# picoAvaR4.net
KiCad netlist of a schematic drawn in EAGLE
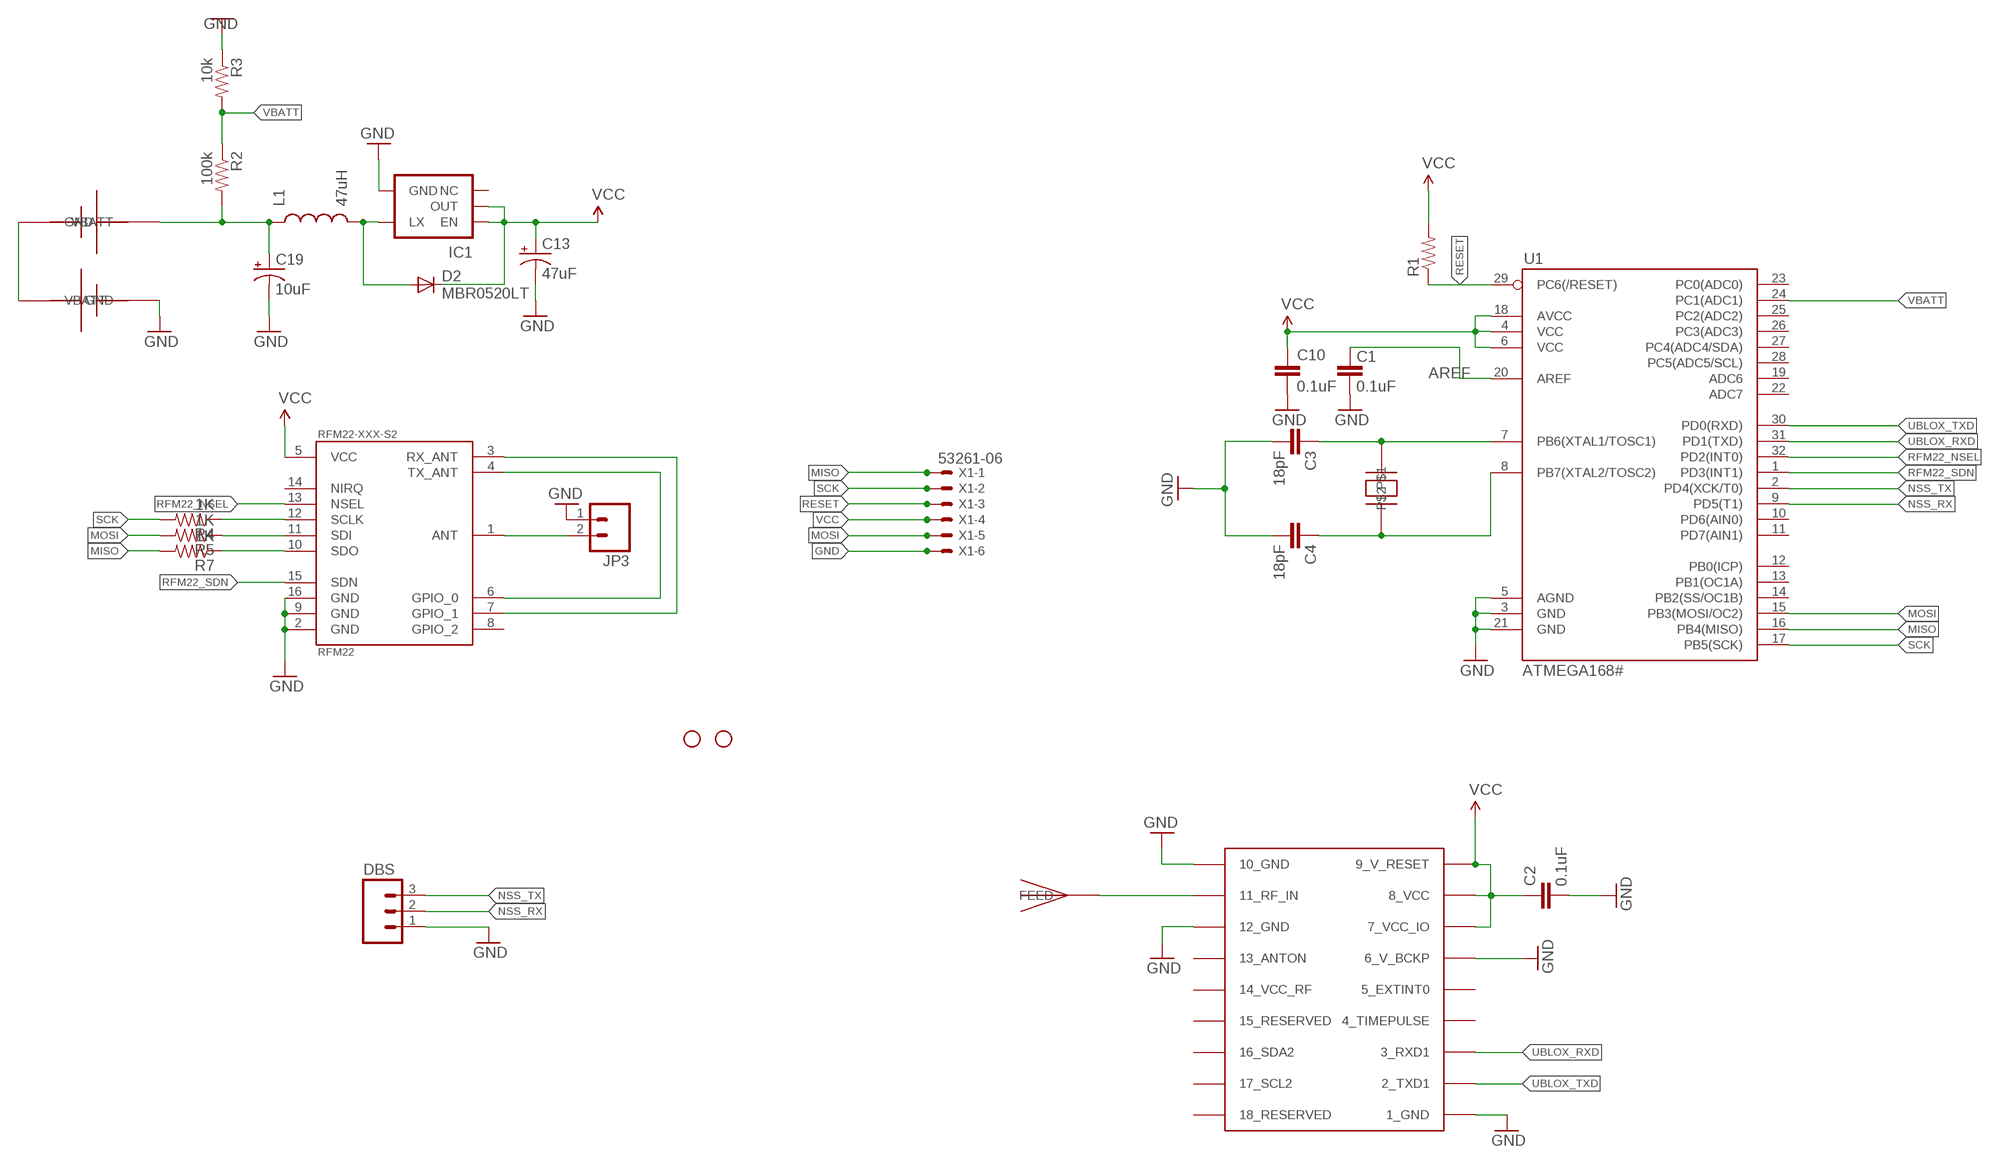
[diagram p0: schematic, sheet 1]

(export (version "E")
  (design (tool "Eeschema 10.0.6"))
  (components
    (comp (ref "C1")
      (value "0.1uF")
      (footprint "eagle-import:0402-CAP")
      (libsource (lib "eagle-import") (part "CAP0402-CAP"))
    )
    (comp (ref "C2")
      (value "0.1uF")
      (footprint "eagle-import:0402-CAP")
      (libsource (lib "eagle-import") (part "CAP0402-CAP"))
    )
    (comp (ref "C3")
      (value "18pF")
      (footprint "eagle-import:0402-CAP")
      (libsource (lib "eagle-import") (part "CAP0402-CAP"))
    )
    (comp (ref "C4")
      (value "18pF")
      (footprint "eagle-import:0402-CAP")
      (libsource (lib "eagle-import") (part "CAP0402-CAP"))
    )
    (comp (ref "C10")
      (value "0.1uF")
      (footprint "eagle-import:0402-CAP")
      (libsource (lib "eagle-import") (part "CAP0402-CAP"))
    )
    (comp (ref "C13")
      (value "47uF")
      (footprint "eagle-import:EIA3216")
      (libsource (lib "eagle-import") (part "CAP_POL1206"))
    )
    (comp (ref "C19")
      (value "10uF")
      (footprint "eagle-import:EIA3216")
      (libsource (lib "eagle-import") (part "CAP_POL1206"))
    )
    (comp (ref "D2")
      (value "MBR0520LT")
      (footprint "eagle-import:SOD123")
      (libsource (lib "eagle-import") (part "MBR0520LT"))
    )
    (comp (ref "DBS")
      (value "M03PTH")
      (footprint "eagle-import:1X03")
      (libsource (lib "eagle-import") (part "M03PTH"))
    )
    (comp (ref "IC1")
      (value "V_REG_NCP1400SOT23-5")
      (footprint "eagle-import:SOT23-5")
      (libsource (lib "eagle-import") (part "V_REG_NCP1400SOT23-5"))
    )
    (comp (ref "JP1")
      (value "STAND-OFF")
      (footprint "eagle-import:STAND-OFF")
      (libsource (lib "eagle-import") (part "STAND-OFF"))
    )
    (comp (ref "JP2")
      (value "STAND-OFF")
      (footprint "eagle-import:STAND-OFF")
      (libsource (lib "eagle-import") (part "STAND-OFF"))
    )
    (comp (ref "JP3")
      (value "M02PTH")
      (footprint "eagle-import:1X02")
      (libsource (lib "eagle-import") (part "M02PTH"))
    )
    (comp (ref "L1")
      (value "47uH")
      (footprint "eagle-import:1210")
      (libsource (lib "eagle-import") (part "INDUCTOR1210"))
    )
    (comp (ref "R1")
      (value "RESISTOR0402-RES")
      (footprint "eagle-import:0402-RES")
      (libsource (lib "eagle-import") (part "RESISTOR0402-RES"))
    )
    (comp (ref "R2")
      (value "100k")
      (footprint "eagle-import:0402-RES")
      (libsource (lib "eagle-import") (part "RESISTOR0402-RES"))
    )
    (comp (ref "R3")
      (value "10k")
      (footprint "eagle-import:0402-RES")
      (libsource (lib "eagle-import") (part "RESISTOR0402-RES"))
    )
    (comp (ref "R4")
      (value "1K")
      (footprint "eagle-import:0402-RES")
      (libsource (lib "eagle-import") (part "RESISTOR0402-RES"))
    )
    (comp (ref "R5")
      (value "1K")
      (footprint "eagle-import:0402-RES")
      (libsource (lib "eagle-import") (part "RESISTOR0402-RES"))
    )
    (comp (ref "R7")
      (value "1K")
      (footprint "eagle-import:0402-RES")
      (libsource (lib "eagle-import") (part "RESISTOR0402-RES"))
    )
    (comp (ref "RFM22-XXX-S2")
      (value "RFM22")
      (footprint "eagle-import:RFM22-XXX-S2")
      (libsource (lib "eagle-import") (part "RFM22"))
    )
    (comp (ref "U$1")
      (value "UBLOX_MAX-6")
      (footprint "eagle-import:UBLOX_MAX-6")
      (libsource (lib "eagle-import") (part "UBLOX_MAX-6"))
    )
    (comp (ref "U$2")
      (value "ABRACON_ABM3_CRYSTAL")
      (footprint "eagle-import:ABRACON_ABM3_CRYSTAL")
      (libsource (lib "eagle-import") (part "ABRACON_ABM3_CRYSTAL"))
    )
    (comp (ref "U$3")
      (value "JTI_ANTENNA-1575AT43A40")
      (footprint "eagle-import:JTI_ANTENNA-1575AT43A40")
      (libsource (lib "eagle-import") (part "JTI_ANTENNA-1575AT43A40"))
    )
    (comp (ref "U$4")
      (value "KEYSTONE-82-AAA-BATTERY-HOLDER")
      (footprint "eagle-import:KEYSTONE-82-AAA-BATTERY")
      (libsource (lib "eagle-import") (part "KEYSTONE-82-AAA-BATTERY-HOLDER"))
    )
    (comp (ref "U$5")
      (value "KEYSTONE-82-AAA-BATTERY-HOLDER")
      (footprint "eagle-import:KEYSTONE-82-AAA-BATTERY")
      (libsource (lib "eagle-import") (part "KEYSTONE-82-AAA-BATTERY-HOLDER"))
    )
    (comp (ref "U1")
      (value "ATMEGA168#")
      (footprint "eagle-import:TQFP32-08")
      (libsource (lib "eagle-import") (part "ATMEGA168"))
    )
    (comp (ref "X1")
      (value "53261-06")
      (footprint "eagle-import:53261-06")
      (libsource (lib "eagle-import") (part "53?-06261"))
    )
  )
  (nets
    (net (code "1") (name "/AREF") (class "Default")
      (node (ref "C1") (pin "2") (pinfunction "2_2") (pintype "passive"))
      (node (ref "U1") (pin "20") (pinfunction "AREF_20") (pintype "bidirectional"))
    )
    (net (code "2") (name "GND") (class "Default")
      (node (ref "C1") (pin "1") (pinfunction "1_1") (pintype "passive"))
      (node (ref "C10") (pin "2") (pinfunction "2_2") (pintype "passive"))
      (node (ref "C13") (pin "C") (pinfunction "-_C") (pintype "passive"))
      (node (ref "C19") (pin "C") (pinfunction "-_C") (pintype "passive"))
      (node (ref "C2") (pin "2") (pinfunction "2_2") (pintype "passive"))
      (node (ref "C3") (pin "2") (pinfunction "2_2") (pintype "passive"))
      (node (ref "C4") (pin "2") (pinfunction "2_2") (pintype "passive"))
      (node (ref "DBS") (pin "1") (pinfunction "1_1") (pintype "passive"))
      (node (ref "IC1") (pin "4") (pinfunction "GND_4") (pintype "input"))
      (node (ref "JP3") (pin "1") (pinfunction "1_1") (pintype "passive"))
      (node (ref "R3") (pin "1") (pinfunction "1_1") (pintype "passive"))
      (node (ref "RFM22-XXX-S2") (pin "16") (pinfunction "GND_16") (pintype "power_in"))
      (node (ref "RFM22-XXX-S2") (pin "2") (pinfunction "GND_2") (pintype "power_in"))
      (node (ref "RFM22-XXX-S2") (pin "9") (pinfunction "GND_9") (pintype "power_in"))
      (node (ref "U$1") (pin "10_GND") (pinfunction "10_GND_10_GND") (pintype "bidirectional"))
      (node (ref "U$1") (pin "12_GND") (pinfunction "12_GND_12_GND") (pintype "bidirectional"))
      (node (ref "U$1") (pin "1_GND") (pinfunction "1_GND_1_GND") (pintype "bidirectional"))
      (node (ref "U$1") (pin "6_V_BCKP") (pinfunction "6_V_BCKP_6_V_BCKP") (pintype "bidirectional"))
      (node (ref "U$5") (pin "GND") (pinfunction "GND_GND") (pintype "bidirectional"))
      (node (ref "U$5") (pin "GND2") (pinfunction "GND_GND2") (pintype "bidirectional"))
      (node (ref "U1") (pin "21") (pinfunction "GND_21") (pintype "bidirectional"))
      (node (ref "U1") (pin "3") (pinfunction "GND_3") (pintype "bidirectional"))
      (node (ref "U1") (pin "5") (pinfunction "AGND_5") (pintype "bidirectional"))
      (node (ref "X1") (pin "6") (pinfunction "S_6") (pintype "passive"))
    )
    (net (code "3") (name "MISO") (class "Default")
      (node (ref "R7") (pin "2") (pinfunction "2_2") (pintype "passive"))
      (node (ref "U1") (pin "16") (pinfunction "PB4(MISO)_16") (pintype "bidirectional"))
      (node (ref "X1") (pin "1") (pinfunction "S_1") (pintype "passive"))
    )
    (net (code "4") (name "MOSI") (class "Default")
      (node (ref "R5") (pin "2") (pinfunction "2_2") (pintype "passive"))
      (node (ref "U1") (pin "15") (pinfunction "PB3(MOSI/OC2)_15") (pintype "bidirectional"))
      (node (ref "X1") (pin "5") (pinfunction "S_5") (pintype "passive"))
    )
    (net (code "5") (name "NSS_RX") (class "Default")
      (node (ref "DBS") (pin "2") (pinfunction "2_2") (pintype "passive"))
      (node (ref "U1") (pin "9") (pinfunction "PD5(T1)_9") (pintype "bidirectional"))
    )
    (net (code "6") (name "NSS_TX") (class "Default")
      (node (ref "DBS") (pin "3") (pinfunction "3_3") (pintype "passive"))
      (node (ref "U1") (pin "2") (pinfunction "PD4(XCK/T0)_2") (pintype "bidirectional"))
    )
    (net (code "7") (name "Net-(C19-+)") (class "Default")
      (node (ref "C19") (pin "A") (pinfunction "+_A") (pintype "passive"))
      (node (ref "L1") (pin "1") (pinfunction "1_1") (pintype "passive"))
      (node (ref "R2") (pin "2") (pinfunction "2_2") (pintype "passive"))
      (node (ref "U$4") (pin "VBATT") (pinfunction "VBATT_VBATT") (pintype "bidirectional"))
      (node (ref "U$4") (pin "VBATT1") (pinfunction "VBATT_VBATT1") (pintype "bidirectional"))
    )
    (net (code "8") (name "Net-(IC1-LX)") (class "Default")
      (node (ref "D2") (pin "A") (pinfunction "A_A") (pintype "passive"))
      (node (ref "IC1") (pin "5") (pinfunction "LX_5") (pintype "input"))
      (node (ref "L1") (pin "2") (pinfunction "2_2") (pintype "passive"))
    )
    (net (code "9") (name "Net-(RFM22-XXX-S2-ANT)") (class "Default")
      (node (ref "JP3") (pin "2") (pinfunction "2_2") (pintype "passive"))
      (node (ref "RFM22-XXX-S2") (pin "1") (pinfunction "ANT_1") (pintype "bidirectional"))
    )
    (net (code "10") (name "Net-(RFM22-XXX-S2-GPIO_0)") (class "Default")
      (node (ref "RFM22-XXX-S2") (pin "4") (pinfunction "TX_ANT_4") (pintype "input"))
      (node (ref "RFM22-XXX-S2") (pin "6") (pinfunction "GPIO_0_6") (pintype "bidirectional"))
    )
    (net (code "11") (name "Net-(RFM22-XXX-S2-GPIO_1)") (class "Default")
      (node (ref "RFM22-XXX-S2") (pin "3") (pinfunction "RX_ANT_3") (pintype "input"))
      (node (ref "RFM22-XXX-S2") (pin "7") (pinfunction "GPIO_1_7") (pintype "bidirectional"))
    )
    (net (code "12") (name "Net-(RFM22-XXX-S2-SCLK)") (class "Default")
      (node (ref "R4") (pin "1") (pinfunction "1_1") (pintype "passive"))
      (node (ref "RFM22-XXX-S2") (pin "12") (pinfunction "SCLK_12") (pintype "input"))
    )
    (net (code "13") (name "Net-(RFM22-XXX-S2-SDI)") (class "Default")
      (node (ref "R5") (pin "1") (pinfunction "1_1") (pintype "passive"))
      (node (ref "RFM22-XXX-S2") (pin "11") (pinfunction "SDI_11") (pintype "input"))
    )
    (net (code "14") (name "Net-(RFM22-XXX-S2-SDO)") (class "Default")
      (node (ref "R7") (pin "1") (pinfunction "1_1") (pintype "passive"))
      (node (ref "RFM22-XXX-S2") (pin "10") (pinfunction "SDO_10") (pintype "output"))
    )
    (net (code "15") (name "Net-(U$1-Pad11_RF_IN)") (class "Default")
      (node (ref "U$1") (pin "11_RF_IN") (pinfunction "11_RF_IN_11_RF_IN") (pintype "bidirectional"))
      (node (ref "U$3") (pin "FEED") (pinfunction "FEED_FEED") (pintype "bidirectional"))
    )
    (net (code "16") (name "Net-(U$4-GND-PadGND2)") (class "Default")
      (node (ref "U$4") (pin "GND") (pinfunction "GND_GND") (pintype "bidirectional"))
      (node (ref "U$4") (pin "GND2") (pinfunction "GND_GND2") (pintype "bidirectional"))
      (node (ref "U$5") (pin "VBATT") (pinfunction "VBATT_VBATT") (pintype "bidirectional"))
      (node (ref "U$5") (pin "VBATT1") (pinfunction "VBATT_VBATT1") (pintype "bidirectional"))
    )
    (net (code "17") (name "Net-(U1-PB6(XTAL1{slash}TOSC1))") (class "Default")
      (node (ref "C3") (pin "1") (pinfunction "1_1") (pintype "passive"))
      (node (ref "U$2") (pin "P$2") (pinfunction "P$2_P$2") (pintype "bidirectional"))
      (node (ref "U1") (pin "7") (pinfunction "PB6(XTAL1/TOSC1)_7") (pintype "bidirectional"))
    )
    (net (code "18") (name "Net-(U1-PB7(XTAL2{slash}TOSC2))") (class "Default")
      (node (ref "C4") (pin "1") (pinfunction "1_1") (pintype "passive"))
      (node (ref "U$2") (pin "P$1") (pinfunction "P$1_P$1") (pintype "bidirectional"))
      (node (ref "U1") (pin "8") (pinfunction "PB7(XTAL2/TOSC2)_8") (pintype "bidirectional"))
    )
    (net (code "19") (name "RESET") (class "Default")
      (node (ref "R1") (pin "1") (pinfunction "1_1") (pintype "passive"))
      (node (ref "U1") (pin "29") (pinfunction "PC6(/RESET)_29") (pintype "bidirectional"))
      (node (ref "X1") (pin "3") (pinfunction "S_3") (pintype "passive"))
    )
    (net (code "20") (name "RFM22_NSEL") (class "Default")
      (node (ref "RFM22-XXX-S2") (pin "13") (pinfunction "NSEL_13") (pintype "input"))
      (node (ref "U1") (pin "32") (pinfunction "PD2(INT0)_32") (pintype "bidirectional"))
    )
    (net (code "21") (name "RFM22_SDN") (class "Default")
      (node (ref "RFM22-XXX-S2") (pin "15") (pinfunction "SDN_15") (pintype "input"))
      (node (ref "U1") (pin "1") (pinfunction "PD3(INT1)_1") (pintype "bidirectional"))
    )
    (net (code "22") (name "SCK") (class "Default")
      (node (ref "R4") (pin "2") (pinfunction "2_2") (pintype "passive"))
      (node (ref "U1") (pin "17") (pinfunction "PB5(SCK)_17") (pintype "bidirectional"))
      (node (ref "X1") (pin "2") (pinfunction "S_2") (pintype "passive"))
    )
    (net (code "23") (name "UBLOX_RXD") (class "Default")
      (node (ref "U$1") (pin "3_RXD1") (pinfunction "3_RXD1_3_RXD1") (pintype "bidirectional"))
      (node (ref "U1") (pin "31") (pinfunction "PD1(TXD)_31") (pintype "bidirectional"))
    )
    (net (code "24") (name "UBLOX_TXD") (class "Default")
      (node (ref "U$1") (pin "2_TXD1") (pinfunction "2_TXD1_2_TXD1") (pintype "bidirectional"))
      (node (ref "U1") (pin "30") (pinfunction "PD0(RXD)_30") (pintype "bidirectional"))
    )
    (net (code "25") (name "VBATT") (class "Default")
      (node (ref "R2") (pin "1") (pinfunction "1_1") (pintype "passive"))
      (node (ref "R3") (pin "2") (pinfunction "2_2") (pintype "passive"))
      (node (ref "U1") (pin "24") (pinfunction "PC1(ADC1)_24") (pintype "bidirectional"))
    )
    (net (code "26") (name "VCC") (class "Default")
      (node (ref "C10") (pin "1") (pinfunction "1_1") (pintype "passive"))
      (node (ref "C13") (pin "A") (pinfunction "+_A") (pintype "passive"))
      (node (ref "C2") (pin "1") (pinfunction "1_1") (pintype "passive"))
      (node (ref "D2") (pin "C") (pinfunction "C_C") (pintype "passive"))
      (node (ref "IC1") (pin "1") (pinfunction "EN_1") (pintype "input"))
      (node (ref "IC1") (pin "2") (pinfunction "OUT_2") (pintype "passive"))
      (node (ref "R1") (pin "2") (pinfunction "2_2") (pintype "passive"))
      (node (ref "RFM22-XXX-S2") (pin "5") (pinfunction "VCC_5") (pintype "bidirectional"))
      (node (ref "U$1") (pin "7_VCC_IO") (pinfunction "7_VCC_IO_7_VCC_IO") (pintype "bidirectional"))
      (node (ref "U$1") (pin "8_VCC") (pinfunction "8_VCC_8_VCC") (pintype "bidirectional"))
      (node (ref "U$1") (pin "9_V_RESET") (pinfunction "9_V_RESET_9_V_RESET") (pintype "bidirectional"))
      (node (ref "U1") (pin "18") (pinfunction "AVCC_18") (pintype "bidirectional"))
      (node (ref "U1") (pin "4") (pinfunction "VCC_4") (pintype "bidirectional"))
      (node (ref "U1") (pin "6") (pinfunction "VCC_6") (pintype "bidirectional"))
      (node (ref "X1") (pin "4") (pinfunction "S_4") (pintype "passive"))
    )
    (net (code "27") (name "unconnected-(IC1-NC-Pad3)") (class "Default")
      (node (ref "IC1") (pin "3") (pinfunction "NC_3") (pintype "input"))
    )
    (net (code "28") (name "unconnected-(RFM22-XXX-S2-GPIO_2-Pad8)") (class "Default")
      (node (ref "RFM22-XXX-S2") (pin "8") (pinfunction "GPIO_2_8") (pintype "bidirectional"))
    )
    (net (code "29") (name "unconnected-(RFM22-XXX-S2-NIRQ-Pad14)") (class "Default")
      (node (ref "RFM22-XXX-S2") (pin "14") (pinfunction "NIRQ_14") (pintype "output"))
    )
    (net (code "30") (name "unconnected-(U$1-Pad4_TIMEPULSE)") (class "Default")
      (node (ref "U$1") (pin "4_TIMEPULSE") (pinfunction "4_TIMEPULSE_4_TIMEPULSE") (pintype "bidirectional"))
    )
    (net (code "31") (name "unconnected-(U$1-Pad5_EXTINT0)") (class "Default")
      (node (ref "U$1") (pin "5_EXTINT0") (pinfunction "5_EXTINT0_5_EXTINT0") (pintype "bidirectional"))
    )
    (net (code "32") (name "unconnected-(U$1-Pad13_ANTON)") (class "Default")
      (node (ref "U$1") (pin "13_ANTON") (pinfunction "13_ANTON_13_ANTON") (pintype "bidirectional"))
    )
    (net (code "33") (name "unconnected-(U$1-Pad14_VCC_RF)") (class "Default")
      (node (ref "U$1") (pin "14_VCC_RF") (pinfunction "14_VCC_RF_14_VCC_RF") (pintype "bidirectional"))
    )
    (net (code "34") (name "unconnected-(U$1-Pad15_RESERVED)") (class "Default")
      (node (ref "U$1") (pin "15_RESERVED") (pinfunction "15_RESERVED_15_RESERVED") (pintype "bidirectional"))
    )
    (net (code "35") (name "unconnected-(U$1-Pad16_SDA2)") (class "Default")
      (node (ref "U$1") (pin "16_SDA2") (pinfunction "16_SDA2_16_SDA2") (pintype "bidirectional"))
    )
    (net (code "36") (name "unconnected-(U$1-Pad17_SCL2)") (class "Default")
      (node (ref "U$1") (pin "17_SCL2") (pinfunction "17_SCL2_17_SCL2") (pintype "bidirectional"))
    )
    (net (code "37") (name "unconnected-(U$1-Pad18_RESERVED)") (class "Default")
      (node (ref "U$1") (pin "18_RESERVED") (pinfunction "18_RESERVED_18_RESERVED") (pintype "bidirectional"))
    )
    (net (code "38") (name "unconnected-(U1-ADC6-Pad19)") (class "Default")
      (node (ref "U1") (pin "19") (pinfunction "ADC6_19") (pintype "bidirectional"))
    )
    (net (code "39") (name "unconnected-(U1-ADC7-Pad22)") (class "Default")
      (node (ref "U1") (pin "22") (pinfunction "ADC7_22") (pintype "bidirectional"))
    )
    (net (code "40") (name "unconnected-(U1-PB0(ICP)-Pad12)") (class "Default")
      (node (ref "U1") (pin "12") (pinfunction "PB0(ICP)_12") (pintype "bidirectional"))
    )
    (net (code "41") (name "unconnected-(U1-PB1(OC1A)-Pad13)") (class "Default")
      (node (ref "U1") (pin "13") (pinfunction "PB1(OC1A)_13") (pintype "bidirectional"))
    )
    (net (code "42") (name "unconnected-(U1-PB2(SS{slash}OC1B)-Pad14)") (class "Default")
      (node (ref "U1") (pin "14") (pinfunction "PB2(SS/OC1B)_14") (pintype "bidirectional"))
    )
    (net (code "43") (name "unconnected-(U1-PC0(ADC0)-Pad23)") (class "Default")
      (node (ref "U1") (pin "23") (pinfunction "PC0(ADC0)_23") (pintype "bidirectional"))
    )
    (net (code "44") (name "unconnected-(U1-PC2(ADC2)-Pad25)") (class "Default")
      (node (ref "U1") (pin "25") (pinfunction "PC2(ADC2)_25") (pintype "bidirectional"))
    )
    (net (code "45") (name "unconnected-(U1-PC3(ADC3)-Pad26)") (class "Default")
      (node (ref "U1") (pin "26") (pinfunction "PC3(ADC3)_26") (pintype "bidirectional"))
    )
    (net (code "46") (name "unconnected-(U1-PC4(ADC4{slash}SDA)-Pad27)") (class "Default")
      (node (ref "U1") (pin "27") (pinfunction "PC4(ADC4/SDA)_27") (pintype "bidirectional"))
    )
    (net (code "47") (name "unconnected-(U1-PC5(ADC5{slash}SCL)-Pad28)") (class "Default")
      (node (ref "U1") (pin "28") (pinfunction "PC5(ADC5/SCL)_28") (pintype "bidirectional"))
    )
    (net (code "48") (name "unconnected-(U1-PD6(AIN0)-Pad10)") (class "Default")
      (node (ref "U1") (pin "10") (pinfunction "PD6(AIN0)_10") (pintype "bidirectional"))
    )
    (net (code "49") (name "unconnected-(U1-PD7(AIN1)-Pad11)") (class "Default")
      (node (ref "U1") (pin "11") (pinfunction "PD7(AIN1)_11") (pintype "bidirectional"))
    )
  )
)
